# unicorder-temp-mk-1_1.net
KiCad netlist of a schematic drawn in EAGLE
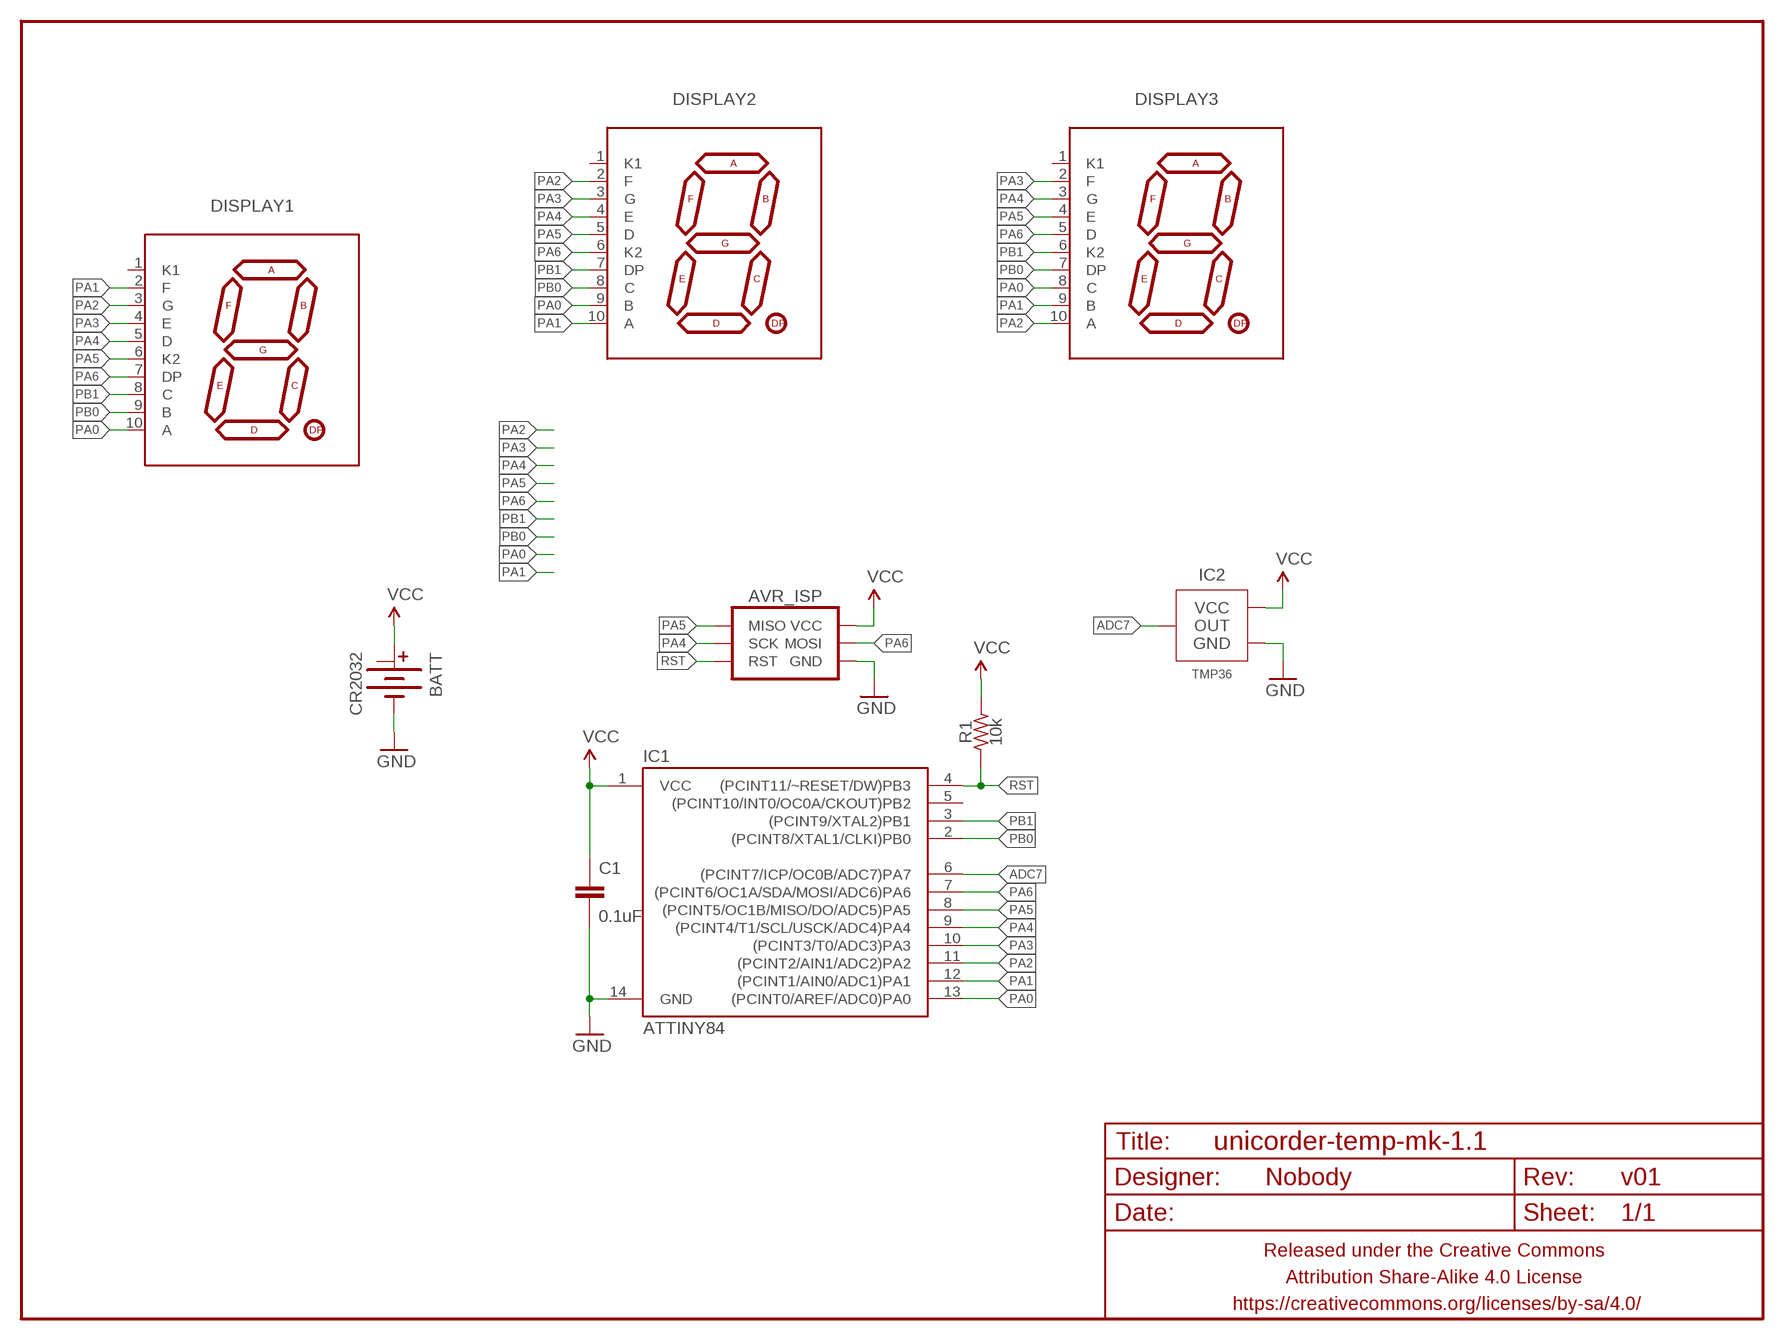
[diagram p0: schematic, sheet 1]

(export (version "E")
  (design (tool "Eeschema 10.0.6"))
  (components
    (comp (ref "AVR_ISP")
      (value "AVR_SPI_PRG_6PTH")
      (footprint "eagle-import:2X3")
      (libsource (lib "eagle-import") (part "AVR_SPI_PRG_6PTH"))
    )
    (comp (ref "BATT")
      (value "CR2032")
      (footprint "eagle-import:BATTCON_20MM_MINE")
      (libsource (lib "eagle-import") (part "BATTERY-COINCR2032_SMD"))
    )
    (comp (ref "C1")
      (value "0.1uF")
      (footprint "eagle-import:C025-024X044")
      (libsource (lib "eagle-import") (part "CAPACITOR-CERAMIC025-024X044"))
    )
    (comp (ref "DISPLAY1")
      (value "7SEG_1DIG-2")
      (footprint "eagle-import:7SEG_1DIG_10MM")
      (libsource (lib "eagle-import") (part "7SEG_1DIG-2"))
    )
    (comp (ref "DISPLAY2")
      (value "7SEG_1DIG-2")
      (footprint "eagle-import:7SEG_1DIG_10MM")
      (libsource (lib "eagle-import") (part "7SEG_1DIG-2"))
    )
    (comp (ref "DISPLAY3")
      (value "7SEG_1DIG-2")
      (footprint "eagle-import:7SEG_1DIG_10MM")
      (libsource (lib "eagle-import") (part "7SEG_1DIG-2"))
    )
    (comp (ref "FRAME1")
      (value "FRAME-LETTERNO_PACKAGE")
      (footprint "eagle-import:DUMMY")
      (fields (field (name "DESIGNER") "Nobody"))
      (libsource (lib "eagle-import") (part "FRAME-LETTERNO_PACKAGE"))
    )
    (comp (ref "IC1")
      (value "ATTINY84")
      (footprint "eagle-import:DIL14")
      (libsource (lib "eagle-import") (part "ATTINY84ATTINY84-20PU"))
    )
    (comp (ref "IC2")
      (value "TMP36")
      (footprint "eagle-import:TO-92-AMMO")
      (libsource (lib "eagle-import") (part "TMP36TO-92"))
    )
    (comp (ref "R1")
      (value "10k")
      (footprint "eagle-import:RESISTOR-AXIAL-PTH-7.62MM")
      (libsource (lib "eagle-import") (part "RESISTORPTH-AXIAL-7.62MM"))
    )
  )
  (nets
    (net (code "1") (name "ADC7") (class "Default")
      (node (ref "IC1") (pin "6") (pinfunction "(PCINT7/ICP/OC0B/ADC7)PA7_6") (pintype "bidirectional"))
      (node (ref "IC2") (pin "2") (pinfunction "OUT_2") (pintype "bidirectional"))
    )
    (net (code "2") (name "GND") (class "Default")
      (node (ref "AVR_ISP") (pin "6") (pinfunction "GND_6") (pintype "passive"))
      (node (ref "BATT") (pin "BOTTOM") (pinfunction "-_BOTTOM") (pintype "bidirectional"))
      (node (ref "C1") (pin "2") (pinfunction "2_2") (pintype "passive"))
      (node (ref "IC1") (pin "14") (pinfunction "GND_14") (pintype "bidirectional"))
      (node (ref "IC2") (pin "3") (pinfunction "GND_3") (pintype "bidirectional"))
    )
    (net (code "3") (name "PA0") (class "Default")
      (node (ref "DISPLAY1") (pin "10") (pinfunction "A_10") (pintype "bidirectional"))
      (node (ref "DISPLAY2") (pin "9") (pinfunction "B_9") (pintype "bidirectional"))
      (node (ref "DISPLAY3") (pin "8") (pinfunction "C_8") (pintype "bidirectional"))
      (node (ref "IC1") (pin "13") (pinfunction "(PCINT0/AREF/ADC0)PA0_13") (pintype "bidirectional"))
    )
    (net (code "4") (name "PA1") (class "Default")
      (node (ref "DISPLAY1") (pin "2") (pinfunction "F_2") (pintype "bidirectional"))
      (node (ref "DISPLAY2") (pin "10") (pinfunction "A_10") (pintype "bidirectional"))
      (node (ref "DISPLAY3") (pin "9") (pinfunction "B_9") (pintype "bidirectional"))
      (node (ref "IC1") (pin "12") (pinfunction "(PCINT1/AIN0/ADC1)PA1_12") (pintype "bidirectional"))
    )
    (net (code "5") (name "PA2") (class "Default")
      (node (ref "DISPLAY1") (pin "3") (pinfunction "G_3") (pintype "bidirectional"))
      (node (ref "DISPLAY2") (pin "2") (pinfunction "F_2") (pintype "bidirectional"))
      (node (ref "DISPLAY3") (pin "10") (pinfunction "A_10") (pintype "bidirectional"))
      (node (ref "IC1") (pin "11") (pinfunction "(PCINT2/AIN1/ADC2)PA2_11") (pintype "bidirectional"))
    )
    (net (code "6") (name "PA3") (class "Default")
      (node (ref "DISPLAY1") (pin "4") (pinfunction "E_4") (pintype "bidirectional"))
      (node (ref "DISPLAY2") (pin "3") (pinfunction "G_3") (pintype "bidirectional"))
      (node (ref "DISPLAY3") (pin "2") (pinfunction "F_2") (pintype "bidirectional"))
      (node (ref "IC1") (pin "10") (pinfunction "(PCINT3/T0/ADC3)PA3_10") (pintype "bidirectional"))
    )
    (net (code "7") (name "PA4") (class "Default")
      (node (ref "AVR_ISP") (pin "3") (pinfunction "SCK_3") (pintype "passive"))
      (node (ref "DISPLAY1") (pin "5") (pinfunction "D_5") (pintype "bidirectional"))
      (node (ref "DISPLAY2") (pin "4") (pinfunction "E_4") (pintype "bidirectional"))
      (node (ref "DISPLAY3") (pin "3") (pinfunction "G_3") (pintype "bidirectional"))
      (node (ref "IC1") (pin "9") (pinfunction "(PCINT4/T1/SCL/USCK/ADC4)PA4_9") (pintype "bidirectional"))
    )
    (net (code "8") (name "PA5") (class "Default")
      (node (ref "AVR_ISP") (pin "1") (pinfunction "MISO_1") (pintype "passive"))
      (node (ref "DISPLAY1") (pin "6") (pinfunction "K2_6") (pintype "bidirectional"))
      (node (ref "DISPLAY2") (pin "5") (pinfunction "D_5") (pintype "bidirectional"))
      (node (ref "DISPLAY3") (pin "4") (pinfunction "E_4") (pintype "bidirectional"))
      (node (ref "IC1") (pin "8") (pinfunction "(PCINT5/OC1B/MISO/DO/ADC5)PA5_8") (pintype "bidirectional"))
    )
    (net (code "9") (name "PA6") (class "Default")
      (node (ref "AVR_ISP") (pin "4") (pinfunction "MOSI_4") (pintype "passive"))
      (node (ref "DISPLAY1") (pin "7") (pinfunction "DP_7") (pintype "bidirectional"))
      (node (ref "DISPLAY2") (pin "6") (pinfunction "K2_6") (pintype "bidirectional"))
      (node (ref "DISPLAY3") (pin "5") (pinfunction "D_5") (pintype "bidirectional"))
      (node (ref "IC1") (pin "7") (pinfunction "(PCINT6/OC1A/SDA/MOSI/ADC6)PA6_7") (pintype "bidirectional"))
    )
    (net (code "10") (name "PB0") (class "Default")
      (node (ref "DISPLAY1") (pin "9") (pinfunction "B_9") (pintype "bidirectional"))
      (node (ref "DISPLAY2") (pin "8") (pinfunction "C_8") (pintype "bidirectional"))
      (node (ref "DISPLAY3") (pin "7") (pinfunction "DP_7") (pintype "bidirectional"))
      (node (ref "IC1") (pin "2") (pinfunction "(PCINT8/XTAL1/CLKI)PB0_2") (pintype "bidirectional"))
    )
    (net (code "11") (name "PB1") (class "Default")
      (node (ref "DISPLAY1") (pin "8") (pinfunction "C_8") (pintype "bidirectional"))
      (node (ref "DISPLAY2") (pin "7") (pinfunction "DP_7") (pintype "bidirectional"))
      (node (ref "DISPLAY3") (pin "6") (pinfunction "K2_6") (pintype "bidirectional"))
      (node (ref "IC1") (pin "3") (pinfunction "(PCINT9/XTAL2)PB1_3") (pintype "bidirectional"))
    )
    (net (code "12") (name "RST") (class "Default")
      (node (ref "AVR_ISP") (pin "5") (pinfunction "RST_5") (pintype "passive"))
      (node (ref "IC1") (pin "4") (pinfunction "(PCINT11/~{RESET/DW})PB3_4") (pintype "bidirectional"))
      (node (ref "R1") (pin "P$1") (pinfunction "1_P$1") (pintype "passive"))
    )
    (net (code "13") (name "VCC") (class "Default")
      (node (ref "AVR_ISP") (pin "2") (pinfunction "VCC_2") (pintype "passive"))
      (node (ref "BATT") (pin "TOP@1") (pinfunction "+_TOP@1") (pintype "bidirectional"))
      (node (ref "C1") (pin "1") (pinfunction "1_1") (pintype "passive"))
      (node (ref "IC1") (pin "1") (pinfunction "VCC_1") (pintype "bidirectional"))
      (node (ref "IC2") (pin "1") (pinfunction "VCC_1") (pintype "bidirectional"))
      (node (ref "R1") (pin "P$2") (pinfunction "2_P$2") (pintype "passive"))
    )
    (net (code "14") (name "unconnected-(BATT-+1-PadTOP@2)") (class "Default")
      (node (ref "BATT") (pin "TOP@2") (pinfunction "+1_TOP@2") (pintype "bidirectional"))
    )
    (net (code "15") (name "unconnected-(DISPLAY1-K1-Pad1)") (class "Default")
      (node (ref "DISPLAY1") (pin "1") (pinfunction "K1_1") (pintype "bidirectional"))
    )
    (net (code "16") (name "unconnected-(DISPLAY2-K1-Pad1)") (class "Default")
      (node (ref "DISPLAY2") (pin "1") (pinfunction "K1_1") (pintype "bidirectional"))
    )
    (net (code "17") (name "unconnected-(DISPLAY3-K1-Pad1)") (class "Default")
      (node (ref "DISPLAY3") (pin "1") (pinfunction "K1_1") (pintype "bidirectional"))
    )
    (net (code "18") (name "unconnected-(IC1-(PCINT10{slash}INT0{slash}OC0A{slash}CKOUT)PB2-Pad5)") (class "Default")
      (node (ref "IC1") (pin "5") (pinfunction "(PCINT10/INT0/OC0A/CKOUT)PB2_5") (pintype "bidirectional"))
    )
  )
)
